# untitled.net
KiCad netlist of a schematic drawn in EAGLE
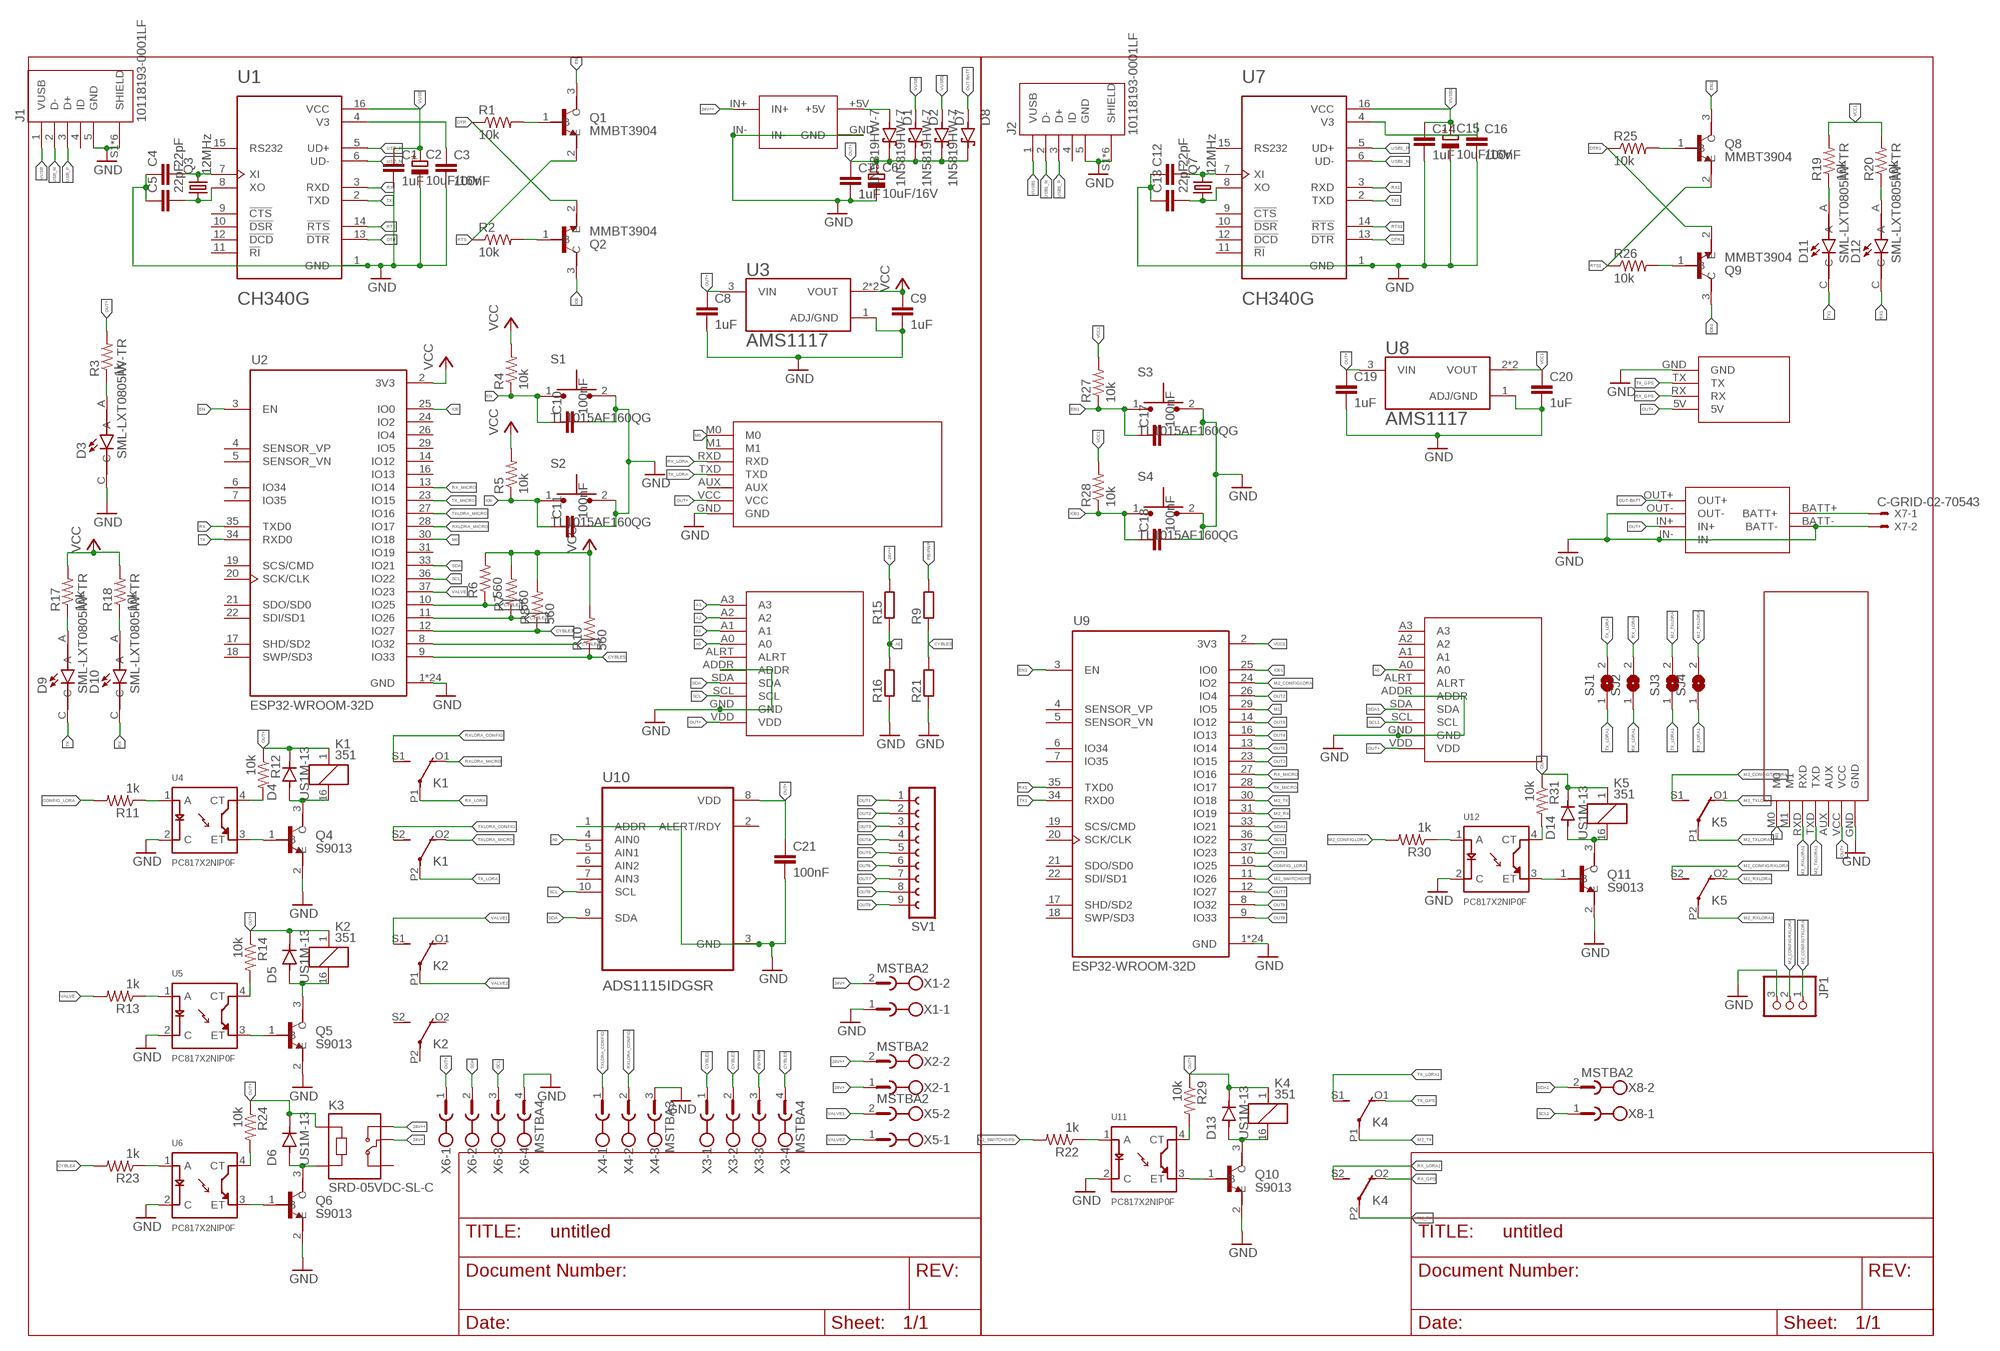
[diagram p0: schematic, sheet 1]

(export (version "E")
  (design (tool "Eeschema 10.0.6"))
  (components
    (comp (ref "ADS1")
      (value "ADS1115")
      (footprint "eagle-import:ADS1115")
      (libsource (lib "eagle-import") (part "ADS1115"))
    )
    (comp (ref "ADS2")
      (value "ADS1115")
      (footprint "eagle-import:ADS1115")
      (libsource (lib "eagle-import") (part "ADS1115"))
    )
    (comp (ref "C1")
      (value "1uF")
      (footprint "eagle-import:C0805K")
      (libsource (lib "eagle-import") (part "C-EUC0805K"))
    )
    (comp (ref "C2")
      (value "10uF/16V")
      (footprint "eagle-import:153CLV-0505")
      (libsource (lib "eagle-import") (part "CPOL-EU153CLV-0505"))
    )
    (comp (ref "C3")
      (value "100nF")
      (footprint "eagle-import:C0805K")
      (libsource (lib "eagle-import") (part "C-EUC0805K"))
    )
    (comp (ref "C4")
      (value "22pF")
      (footprint "eagle-import:C0805K")
      (libsource (lib "eagle-import") (part "C-EUC0805K"))
    )
    (comp (ref "C5")
      (value "22pF")
      (footprint "eagle-import:C0805K")
      (libsource (lib "eagle-import") (part "C-EUC0805K"))
    )
    (comp (ref "C6")
      (value "10uF/16V")
      (footprint "eagle-import:153CLV-0505")
      (libsource (lib "eagle-import") (part "CPOL-EU153CLV-0505"))
    )
    (comp (ref "C7")
      (value "1uF")
      (footprint "eagle-import:C0805K")
      (libsource (lib "eagle-import") (part "C-EUC0805K"))
    )
    (comp (ref "C8")
      (value "1uF")
      (footprint "eagle-import:C0805K")
      (libsource (lib "eagle-import") (part "C-EUC0805K"))
    )
    (comp (ref "C9")
      (value "1uF")
      (footprint "eagle-import:C0805K")
      (libsource (lib "eagle-import") (part "C-EUC0805K"))
    )
    (comp (ref "C10")
      (value "100nF")
      (footprint "eagle-import:C0805K")
      (libsource (lib "eagle-import") (part "C-EUC0805K"))
    )
    (comp (ref "C11")
      (value "100nF")
      (footprint "eagle-import:C0805K")
      (libsource (lib "eagle-import") (part "C-EUC0805K"))
    )
    (comp (ref "C12")
      (value "22pF")
      (footprint "eagle-import:C0805K")
      (libsource (lib "eagle-import") (part "C-EUC0805K"))
    )
    (comp (ref "C13")
      (value "22pF")
      (footprint "eagle-import:C0805K")
      (libsource (lib "eagle-import") (part "C-EUC0805K"))
    )
    (comp (ref "C14")
      (value "1uF")
      (footprint "eagle-import:C0805K")
      (libsource (lib "eagle-import") (part "C-EUC0805K"))
    )
    (comp (ref "C15")
      (value "10uF/16V")
      (footprint "eagle-import:153CLV-0505")
      (libsource (lib "eagle-import") (part "CPOL-EU153CLV-0505"))
    )
    (comp (ref "C16")
      (value "100nF")
      (footprint "eagle-import:C0805K")
      (libsource (lib "eagle-import") (part "C-EUC0805K"))
    )
    (comp (ref "C17")
      (value "100nF")
      (footprint "eagle-import:C0805K")
      (libsource (lib "eagle-import") (part "C-EUC0805K"))
    )
    (comp (ref "C18")
      (value "100nF")
      (footprint "eagle-import:C0805K")
      (libsource (lib "eagle-import") (part "C-EUC0805K"))
    )
    (comp (ref "C19")
      (value "1uF")
      (footprint "eagle-import:C0805K")
      (libsource (lib "eagle-import") (part "C-EUC0805K"))
    )
    (comp (ref "C20")
      (value "1uF")
      (footprint "eagle-import:C0805K")
      (libsource (lib "eagle-import") (part "C-EUC0805K"))
    )
    (comp (ref "C21")
      (value "100nF")
      (footprint "eagle-import:C0805K")
      (libsource (lib "eagle-import") (part "C-EUC0805K"))
    )
    (comp (ref "D1")
      (value "1N5819HW-7")
      (footprint "eagle-import:SOD3715X145N")
      (fields (field (name "MF") "Diodes Inc."))
      (libsource (lib "eagle-import") (part "1N5819HW-7"))
    )
    (comp (ref "D2")
      (value "1N5819HW-7")
      (footprint "eagle-import:SOD3715X145N")
      (fields (field (name "MF") "Diodes Inc."))
      (libsource (lib "eagle-import") (part "1N5819HW-7"))
    )
    (comp (ref "D3")
      (value "SML-LXT0805IW-TR")
      (footprint "eagle-import:LEDC2012X120N")
      (fields (field (name "MF") "Lumex Opto/Components"))
      (libsource (lib "eagle-import") (part "SML-LXT0805IW-TR"))
    )
    (comp (ref "D4")
      (value "US1M-13")
      (footprint "eagle-import:DIOM5226X240N")
      (fields (field (name "MF") "Diodes Incorporated"))
      (libsource (lib "eagle-import") (part "US1M-13"))
    )
    (comp (ref "D5")
      (value "US1M-13")
      (footprint "eagle-import:DIOM5226X240N")
      (fields (field (name "MF") "Diodes Incorporated"))
      (libsource (lib "eagle-import") (part "US1M-13"))
    )
    (comp (ref "D6")
      (value "US1M-13")
      (footprint "eagle-import:DIOM5226X240N")
      (fields (field (name "MF") "Diodes Incorporated"))
      (libsource (lib "eagle-import") (part "US1M-13"))
    )
    (comp (ref "D7")
      (value "1N5819HW-7")
      (footprint "eagle-import:SOD3715X145N")
      (fields (field (name "MF") "Diodes Inc."))
      (libsource (lib "eagle-import") (part "1N5819HW-7"))
    )
    (comp (ref "D8")
      (value "1N5819HW-7")
      (footprint "eagle-import:SOD3715X145N")
      (fields (field (name "MF") "Diodes Inc."))
      (libsource (lib "eagle-import") (part "1N5819HW-7"))
    )
    (comp (ref "D9")
      (value "SML-LXT0805IW-TR")
      (footprint "eagle-import:LEDC2012X120N")
      (fields (field (name "MF") "Lumex Opto/Components"))
      (libsource (lib "eagle-import") (part "SML-LXT0805IW-TR"))
    )
    (comp (ref "D10")
      (value "SML-LXT0805IW-TR")
      (footprint "eagle-import:LEDC2012X120N")
      (fields (field (name "MF") "Lumex Opto/Components"))
      (libsource (lib "eagle-import") (part "SML-LXT0805IW-TR"))
    )
    (comp (ref "D11")
      (value "SML-LXT0805IW-TR")
      (footprint "eagle-import:LEDC2012X120N")
      (fields (field (name "MF") "Lumex Opto/Components"))
      (libsource (lib "eagle-import") (part "SML-LXT0805IW-TR"))
    )
    (comp (ref "D12")
      (value "SML-LXT0805IW-TR")
      (footprint "eagle-import:LEDC2012X120N")
      (fields (field (name "MF") "Lumex Opto/Components"))
      (libsource (lib "eagle-import") (part "SML-LXT0805IW-TR"))
    )
    (comp (ref "D13")
      (value "US1M-13")
      (footprint "eagle-import:DIOM5226X240N")
      (fields (field (name "MF") "Diodes Incorporated"))
      (libsource (lib "eagle-import") (part "US1M-13"))
    )
    (comp (ref "D14")
      (value "US1M-13")
      (footprint "eagle-import:DIOM5226X240N")
      (fields (field (name "MF") "Diodes Incorporated"))
      (libsource (lib "eagle-import") (part "US1M-13"))
    )
    (comp (ref "EBYTEE220-900T22D1")
      (value "EBYTEE220-900T22D")
      (footprint "eagle-import:EBYTEE220-900T22D")
      (libsource (lib "eagle-import") (part "EBYTEE220-900T22D"))
    )
    (comp (ref "EBYTEE220-900T22D2")
      (value "EBYTEE220-900T22D")
      (footprint "eagle-import:EBYTEE220-900T22D")
      (libsource (lib "eagle-import") (part "EBYTEE220-900T22D"))
    )
    (comp (ref "J1")
      (value "10118193-0001LF")
      (footprint "eagle-import:FCI_10118193-0001LF")
      (fields (field (name "MF") "FCI"))
      (libsource (lib "eagle-import") (part "10118193-0001LF"))
    )
    (comp (ref "J2")
      (value "10118193-0001LF")
      (footprint "eagle-import:FCI_10118193-0001LF")
      (fields (field (name "MF") "FCI"))
      (libsource (lib "eagle-import") (part "10118193-0001LF"))
    )
    (comp (ref "JP1")
      (value "PINHD-1X3")
      (footprint "eagle-import:1X03")
      (libsource (lib "eagle-import") (part "PINHD-1X3"))
    )
    (comp (ref "K1")
      (value "351")
      (footprint "eagle-import:351")
      (libsource (lib "eagle-import") (part "351"))
    )
    (comp (ref "K2")
      (value "351")
      (footprint "eagle-import:351")
      (libsource (lib "eagle-import") (part "351"))
    )
    (comp (ref "K3")
      (value "SRD-05VDC-SL-C")
      (footprint "eagle-import:RELAY_SRD-05VDC-SL-C")
      (fields (field (name "MF") "Songle Relay"))
      (libsource (lib "eagle-import") (part "SRD-05VDC-SL-C"))
    )
    (comp (ref "K4")
      (value "351")
      (footprint "eagle-import:351")
      (libsource (lib "eagle-import") (part "351"))
    )
    (comp (ref "K5")
      (value "351")
      (footprint "eagle-import:351")
      (libsource (lib "eagle-import") (part "351"))
    )
    (comp (ref "MODUL-BATT1")
      (value "MODUL-BATT")
      (footprint "eagle-import:MODUL-BATT")
      (libsource (lib "eagle-import") (part "MODUL-BATT"))
    )
    (comp (ref "NEO-6MGPS1")
      (value "NEO-6MGPS")
      (footprint "eagle-import:NEO-6MGPS")
      (libsource (lib "eagle-import") (part "NEO-6MGPS"))
    )
    (comp (ref "Q1")
      (value "MMBT3904")
      (footprint "eagle-import:SOT95P240X120-3N")
      (fields (field (name "MF") "ON Semiconductor"))
      (libsource (lib "eagle-import") (part "MMBT3904"))
    )
    (comp (ref "Q2")
      (value "MMBT3904")
      (footprint "eagle-import:SOT95P240X120-3N")
      (fields (field (name "MF") "ON Semiconductor"))
      (libsource (lib "eagle-import") (part "MMBT3904"))
    )
    (comp (ref "Q3")
      (value "12MHz")
      (footprint "eagle-import:SM49")
      (libsource (lib "eagle-import") (part "CRYSTALSM49"))
    )
    (comp (ref "Q4")
      (value "S9013")
      (footprint "eagle-import:SOT95P240X120-3N")
      (fields (field (name "MF") "JCET"))
      (libsource (lib "eagle-import") (part "S9013"))
    )
    (comp (ref "Q5")
      (value "S9013")
      (footprint "eagle-import:SOT95P240X120-3N")
      (fields (field (name "MF") "JCET"))
      (libsource (lib "eagle-import") (part "S9013"))
    )
    (comp (ref "Q6")
      (value "S9013")
      (footprint "eagle-import:SOT95P240X120-3N")
      (fields (field (name "MF") "JCET"))
      (libsource (lib "eagle-import") (part "S9013"))
    )
    (comp (ref "Q7")
      (value "12MHz")
      (footprint "eagle-import:SM49")
      (libsource (lib "eagle-import") (part "CRYSTALSM49"))
    )
    (comp (ref "Q8")
      (value "MMBT3904")
      (footprint "eagle-import:SOT95P240X120-3N")
      (fields (field (name "MF") "ON Semiconductor"))
      (libsource (lib "eagle-import") (part "MMBT3904"))
    )
    (comp (ref "Q9")
      (value "MMBT3904")
      (footprint "eagle-import:SOT95P240X120-3N")
      (fields (field (name "MF") "ON Semiconductor"))
      (libsource (lib "eagle-import") (part "MMBT3904"))
    )
    (comp (ref "Q10")
      (value "S9013")
      (footprint "eagle-import:SOT95P240X120-3N")
      (fields (field (name "MF") "JCET"))
      (libsource (lib "eagle-import") (part "S9013"))
    )
    (comp (ref "Q11")
      (value "S9013")
      (footprint "eagle-import:SOT95P240X120-3N")
      (fields (field (name "MF") "JCET"))
      (libsource (lib "eagle-import") (part "S9013"))
    )
    (comp (ref "R1")
      (value "10k")
      (footprint "eagle-import:M0805")
      (libsource (lib "eagle-import") (part "R-US_M0805"))
    )
    (comp (ref "R2")
      (value "10k")
      (footprint "eagle-import:M0805")
      (libsource (lib "eagle-import") (part "R-US_M0805"))
    )
    (comp (ref "R3")
      (value "1k")
      (footprint "eagle-import:M0805")
      (libsource (lib "eagle-import") (part "R-US_M0805"))
    )
    (comp (ref "R4")
      (value "10k")
      (footprint "eagle-import:M0805")
      (libsource (lib "eagle-import") (part "R-US_M0805"))
    )
    (comp (ref "R5")
      (value "10k")
      (footprint "eagle-import:M0805")
      (libsource (lib "eagle-import") (part "R-US_M0805"))
    )
    (comp (ref "R6")
      (value "560")
      (footprint "eagle-import:M0805")
      (libsource (lib "eagle-import") (part "R-US_M0805"))
    )
    (comp (ref "R7")
      (value "560")
      (footprint "eagle-import:M0805")
      (libsource (lib "eagle-import") (part "R-US_M0805"))
    )
    (comp (ref "R8")
      (value "560")
      (footprint "eagle-import:M0805")
      (libsource (lib "eagle-import") (part "R-US_M0805"))
    )
    (comp (ref "R9")
      (value "R-EU_0207/12")
      (footprint "eagle-import:0207_12")
      (libsource (lib "eagle-import") (part "R-EU_0207/12"))
    )
    (comp (ref "R10")
      (value "560")
      (footprint "eagle-import:M0805")
      (libsource (lib "eagle-import") (part "R-US_M0805"))
    )
    (comp (ref "R11")
      (value "1k")
      (footprint "eagle-import:M0805")
      (libsource (lib "eagle-import") (part "R-US_M0805"))
    )
    (comp (ref "R12")
      (value "10k")
      (footprint "eagle-import:M0805")
      (libsource (lib "eagle-import") (part "R-US_M0805"))
    )
    (comp (ref "R13")
      (value "1k")
      (footprint "eagle-import:M0805")
      (libsource (lib "eagle-import") (part "R-US_M0805"))
    )
    (comp (ref "R14")
      (value "10k")
      (footprint "eagle-import:M0805")
      (libsource (lib "eagle-import") (part "R-US_M0805"))
    )
    (comp (ref "R15")
      (value "R-EU_0207/12")
      (footprint "eagle-import:0207_12")
      (libsource (lib "eagle-import") (part "R-EU_0207/12"))
    )
    (comp (ref "R16")
      (value "R-EU_0207/12")
      (footprint "eagle-import:0207_12")
      (libsource (lib "eagle-import") (part "R-EU_0207/12"))
    )
    (comp (ref "R17")
      (value "10k")
      (footprint "eagle-import:M0805")
      (libsource (lib "eagle-import") (part "R-US_M0805"))
    )
    (comp (ref "R18")
      (value "10k")
      (footprint "eagle-import:M0805")
      (libsource (lib "eagle-import") (part "R-US_M0805"))
    )
    (comp (ref "R19")
      (value "10k")
      (footprint "eagle-import:M0805")
      (libsource (lib "eagle-import") (part "R-US_M0805"))
    )
    (comp (ref "R20")
      (value "10k")
      (footprint "eagle-import:M0805")
      (libsource (lib "eagle-import") (part "R-US_M0805"))
    )
    (comp (ref "R21")
      (value "R-EU_0207/12")
      (footprint "eagle-import:0207_12")
      (libsource (lib "eagle-import") (part "R-EU_0207/12"))
    )
    (comp (ref "R22")
      (value "1k")
      (footprint "eagle-import:M0805")
      (libsource (lib "eagle-import") (part "R-US_M0805"))
    )
    (comp (ref "R23")
      (value "1k")
      (footprint "eagle-import:M0805")
      (libsource (lib "eagle-import") (part "R-US_M0805"))
    )
    (comp (ref "R24")
      (value "10k")
      (footprint "eagle-import:M0805")
      (libsource (lib "eagle-import") (part "R-US_M0805"))
    )
    (comp (ref "R25")
      (value "10k")
      (footprint "eagle-import:M0805")
      (libsource (lib "eagle-import") (part "R-US_M0805"))
    )
    (comp (ref "R26")
      (value "10k")
      (footprint "eagle-import:M0805")
      (libsource (lib "eagle-import") (part "R-US_M0805"))
    )
    (comp (ref "R27")
      (value "10k")
      (footprint "eagle-import:M0805")
      (libsource (lib "eagle-import") (part "R-US_M0805"))
    )
    (comp (ref "R28")
      (value "10k")
      (footprint "eagle-import:M0805")
      (libsource (lib "eagle-import") (part "R-US_M0805"))
    )
    (comp (ref "R29")
      (value "10k")
      (footprint "eagle-import:M0805")
      (libsource (lib "eagle-import") (part "R-US_M0805"))
    )
    (comp (ref "R30")
      (value "1k")
      (footprint "eagle-import:M0805")
      (libsource (lib "eagle-import") (part "R-US_M0805"))
    )
    (comp (ref "R31")
      (value "10k")
      (footprint "eagle-import:M0805")
      (libsource (lib "eagle-import") (part "R-US_M0805"))
    )
    (comp (ref "S1")
      (value "TL1015AF160QG")
      (footprint "eagle-import:SW_TL1015AF160QG")
      (fields (field (name "MF") "E-Switch"))
      (libsource (lib "eagle-import") (part "TL1015AF160QG"))
    )
    (comp (ref "S2")
      (value "TL1015AF160QG")
      (footprint "eagle-import:SW_TL1015AF160QG")
      (fields (field (name "MF") "E-Switch"))
      (libsource (lib "eagle-import") (part "TL1015AF160QG"))
    )
    (comp (ref "S3")
      (value "TL1015AF160QG")
      (footprint "eagle-import:SW_TL1015AF160QG")
      (fields (field (name "MF") "E-Switch"))
      (libsource (lib "eagle-import") (part "TL1015AF160QG"))
    )
    (comp (ref "S4")
      (value "TL1015AF160QG")
      (footprint "eagle-import:SW_TL1015AF160QG")
      (fields (field (name "MF") "E-Switch"))
      (libsource (lib "eagle-import") (part "TL1015AF160QG"))
    )
    (comp (ref "SJ1") (value "SJ") (footprint "eagle-import:SJ") (libsource (lib "eagle-import") (part "SJ")))
    (comp (ref "SJ2") (value "SJ") (footprint "eagle-import:SJ") (libsource (lib "eagle-import") (part "SJ")))
    (comp (ref "SJ3") (value "SJ") (footprint "eagle-import:SJ") (libsource (lib "eagle-import") (part "SJ")))
    (comp (ref "SJ4") (value "SJ") (footprint "eagle-import:SJ") (libsource (lib "eagle-import") (part "SJ")))
    (comp (ref "SUPER-STEPDOWN1")
      (value "SUPER-STEPDOWN")
      (footprint "eagle-import:SUPER-STEPDOWN")
      (libsource (lib "eagle-import") (part "SUPER-STEPDOWN"))
    )
    (comp (ref "SV1")
      (value "FE09-1")
      (footprint "eagle-import:FE09")
      (libsource (lib "eagle-import") (part "FE09-1"))
    )
    (comp (ref "U1")
      (value "CH340G")
      (footprint "eagle-import:SOIC127P600X180-16N")
      (fields (field (name "MF") "WCH") (field (name "MP") "Ch340G"))
      (libsource (lib "eagle-import") (part "CH340G"))
    )
    (comp (ref "U2")
      (value "ESP32-WROOM-32D")
      (footprint "eagle-import:MODULE_ESP32-WROOM-32D")
      (fields (field (name "MF") "Espressif Systems"))
      (libsource (lib "eagle-import") (part "ESP32-WROOM-32D"))
    )
    (comp (ref "U3")
      (value "AMS1117")
      (footprint "eagle-import:SOT229P700X180-4N")
      (fields (field (name "MF") "Advanced Monolithic Systems"))
      (libsource (lib "eagle-import") (part "AMS1117"))
    )
    (comp (ref "U4")
      (value "PC817X2NIP0F")
      (footprint "eagle-import:SOT254P975X400-4N")
      (fields (field (name "MF") "Sharp Microelectronics"))
      (libsource (lib "eagle-import") (part "PC817X2NIP0F"))
    )
    (comp (ref "U5")
      (value "PC817X2NIP0F")
      (footprint "eagle-import:SOT254P975X400-4N")
      (fields (field (name "MF") "Sharp Microelectronics"))
      (libsource (lib "eagle-import") (part "PC817X2NIP0F"))
    )
    (comp (ref "U6")
      (value "PC817X2NIP0F")
      (footprint "eagle-import:SOT254P975X400-4N")
      (fields (field (name "MF") "Sharp Microelectronics"))
      (libsource (lib "eagle-import") (part "PC817X2NIP0F"))
    )
    (comp (ref "U7")
      (value "CH340G")
      (footprint "eagle-import:SOIC127P600X180-16N")
      (fields (field (name "MF") "WCH") (field (name "MP") "Ch340G"))
      (libsource (lib "eagle-import") (part "CH340G"))
    )
    (comp (ref "U8")
      (value "AMS1117")
      (footprint "eagle-import:SOT229P700X180-4N")
      (fields (field (name "MF") "Advanced Monolithic Systems"))
      (libsource (lib "eagle-import") (part "AMS1117"))
    )
    (comp (ref "U9")
      (value "ESP32-WROOM-32D")
      (footprint "eagle-import:MODULE_ESP32-WROOM-32D")
      (fields (field (name "MF") "Espressif Systems"))
      (libsource (lib "eagle-import") (part "ESP32-WROOM-32D"))
    )
    (comp (ref "U10")
      (value "ADS1115IDGSR")
      (footprint "eagle-import:SOP50P490X110-10N")
      (fields (field (name "MF") "Texas Instruments"))
      (libsource (lib "eagle-import") (part "ADS1115IDGSR"))
    )
    (comp (ref "U11")
      (value "PC817X2NIP0F")
      (footprint "eagle-import:SOT254P975X400-4N")
      (fields (field (name "MF") "Sharp Microelectronics"))
      (libsource (lib "eagle-import") (part "PC817X2NIP0F"))
    )
    (comp (ref "U12")
      (value "PC817X2NIP0F")
      (footprint "eagle-import:SOT254P975X400-4N")
      (fields (field (name "MF") "Sharp Microelectronics"))
      (libsource (lib "eagle-import") (part "PC817X2NIP0F"))
    )
    (comp (ref "X1")
      (value "MSTBA2")
      (footprint "eagle-import:MSTBA2")
      (fields (field (name "MF") "FARNELL") (field (name "MPN") "1757242"))
      (libsource (lib "eagle-import") (part "MSTBA2"))
    )
    (comp (ref "X2")
      (value "MSTBA2")
      (footprint "eagle-import:MSTBA2")
      (fields (field (name "MF") "FARNELL") (field (name "MPN") "1757242"))
      (libsource (lib "eagle-import") (part "MSTBA2"))
    )
    (comp (ref "X3")
      (value "MSTBA4")
      (footprint "eagle-import:MSTBA4")
      (fields (field (name "MF") "FARNELL") (field (name "MPN") "1757268"))
      (libsource (lib "eagle-import") (part "MSTBA4"))
    )
    (comp (ref "X4")
      (value "MSTBA3")
      (footprint "eagle-import:MSTBA3")
      (fields (field (name "MF") "FARNELL") (field (name "MPN") "1757255"))
      (libsource (lib "eagle-import") (part "MSTBA3"))
    )
    (comp (ref "X5")
      (value "MSTBA2")
      (footprint "eagle-import:MSTBA2")
      (fields (field (name "MF") "FARNELL") (field (name "MPN") "1757242"))
      (libsource (lib "eagle-import") (part "MSTBA2"))
    )
    (comp (ref "X6")
      (value "MSTBA4")
      (footprint "eagle-import:MSTBA4")
      (fields (field (name "MF") "FARNELL") (field (name "MPN") "1757268"))
      (libsource (lib "eagle-import") (part "MSTBA4"))
    )
    (comp (ref "X7")
      (value "C-GRID-02-70543")
      (footprint "eagle-import:70543-02")
      (fields (field (name "MF") "MOLEX"))
      (libsource (lib "eagle-import") (part "C-GRID-02-70543"))
    )
    (comp (ref "X8")
      (value "MSTBA2")
      (footprint "eagle-import:MSTBA2")
      (fields (field (name "MF") "FARNELL") (field (name "MPN") "1757242"))
      (libsource (lib "eagle-import") (part "MSTBA2"))
    )
  )
  (nets
    (net (code "1") (name "24V+") (class "Default")
      (node (ref "K3") (pin "COM") (pinfunction "COM_COM") (pintype "passive"))
      (node (ref "X1") (pin "2") (pinfunction "1_2") (pintype "passive"))
      (node (ref "X2") (pin "1") (pinfunction "1_1") (pintype "passive"))
    )
    (net (code "2") (name "24V++") (class "Default")
      (node (ref "K3") (pin "NO") (pinfunction "NO_NO") (pintype "passive"))
      (node (ref "R15") (pin "2") (pinfunction "2_2") (pintype "passive"))
      (node (ref "SUPER-STEPDOWN1") (pin "IN+") (pinfunction "IN+_IN+") (pintype "bidirectional"))
      (node (ref "X2") (pin "2") (pinfunction "1_2") (pintype "passive"))
    )
    (net (code "3") (name "A0") (class "Default")
      (node (ref "ADS1") (pin "A0") (pinfunction "A0_A0") (pintype "bidirectional"))
      (node (ref "ADS2") (pin "A0") (pinfunction "A0_A0") (pintype "bidirectional"))
      (node (ref "R15") (pin "1") (pinfunction "1_1") (pintype "passive"))
      (node (ref "R16") (pin "2") (pinfunction "2_2") (pintype "passive"))
      (node (ref "U10") (pin "4") (pinfunction "AIN0_4") (pintype "input"))
    )
    (net (code "4") (name "A1") (class "Default")
      (node (ref "ADS1") (pin "A1") (pinfunction "A1_A1") (pintype "bidirectional"))
    )
    (net (code "5") (name "A2") (class "Default")
      (node (ref "ADS1") (pin "A2") (pinfunction "A2_A2") (pintype "bidirectional"))
    )
    (net (code "6") (name "A3") (class "Default")
      (node (ref "ADS1") (pin "A3") (pinfunction "A3_A3") (pintype "bidirectional"))
    )
    (net (code "7") (name "CONFIG_LORA") (class "Default")
      (node (ref "R11") (pin "2") (pinfunction "2_2") (pintype "passive"))
      (node (ref "U9") (pin "10") (pinfunction "IO25_10") (pintype "bidirectional"))
    )
    (net (code "8") (name "CYBLE1") (class "Default")
      (node (ref "R6") (pin "1") (pinfunction "1_1") (pintype "passive"))
      (node (ref "U2") (pin "10") (pinfunction "IO25_10") (pintype "bidirectional"))
      (node (ref "X3") (pin "1") (pinfunction "1_1") (pintype "passive"))
    )
    (net (code "9") (name "CYBLE2") (class "Default")
      (node (ref "R7") (pin "1") (pinfunction "1_1") (pintype "passive"))
      (node (ref "U2") (pin "11") (pinfunction "IO26_11") (pintype "bidirectional"))
      (node (ref "X3") (pin "2") (pinfunction "1_2") (pintype "passive"))
    )
    (net (code "10") (name "CYBLE3") (class "Default")
      (node (ref "R21") (pin "2") (pinfunction "2_2") (pintype "passive"))
      (node (ref "R8") (pin "1") (pinfunction "1_1") (pintype "passive"))
      (node (ref "R9") (pin "1") (pinfunction "1_1") (pintype "passive"))
      (node (ref "U2") (pin "12") (pinfunction "IO27_12") (pintype "bidirectional"))
    )
    (net (code "11") (name "CYBLE4") (class "Default")
      (node (ref "R23") (pin "2") (pinfunction "2_2") (pintype "passive"))
      (node (ref "U2") (pin "8") (pinfunction "IO32_8") (pintype "bidirectional"))
    )
    (net (code "12") (name "CYBLE5") (class "Default")
      (node (ref "R10") (pin "1") (pinfunction "1_1") (pintype "passive"))
      (node (ref "U2") (pin "9") (pinfunction "IO33_9") (pintype "bidirectional"))
      (node (ref "X3") (pin "4") (pinfunction "1_4") (pintype "passive"))
    )
    (net (code "13") (name "DTR") (class "Default")
      (node (ref "Q2") (pin "2") (pinfunction "E_2") (pintype "passive"))
      (node (ref "R1") (pin "1") (pinfunction "1_1") (pintype "passive"))
      (node (ref "U1") (pin "13") (pinfunction "~{DTR}_13") (pintype "output"))
    )
    (net (code "14") (name "DTR1") (class "Default")
      (node (ref "Q9") (pin "2") (pinfunction "E_2") (pintype "passive"))
      (node (ref "R25") (pin "1") (pinfunction "1_1") (pintype "passive"))
      (node (ref "U7") (pin "13") (pinfunction "~{DTR}_13") (pintype "output"))
    )
    (net (code "15") (name "EN") (class "Default")
      (node (ref "C10") (pin "1") (pinfunction "1_1") (pintype "passive"))
      (node (ref "Q1") (pin "3") (pinfunction "C_3") (pintype "passive"))
      (node (ref "R4") (pin "1") (pinfunction "1_1") (pintype "passive"))
      (node (ref "S1") (pin "1") (pinfunction "1_1") (pintype "passive"))
      (node (ref "U2") (pin "3") (pinfunction "EN_3") (pintype "input"))
    )
    (net (code "16") (name "EN1") (class "Default")
      (node (ref "C17") (pin "1") (pinfunction "1_1") (pintype "passive"))
      (node (ref "Q8") (pin "3") (pinfunction "C_3") (pintype "passive"))
      (node (ref "R27") (pin "1") (pinfunction "1_1") (pintype "passive"))
      (node (ref "S3") (pin "1") (pinfunction "1_1") (pintype "passive"))
      (node (ref "U9") (pin "3") (pinfunction "EN_3") (pintype "input"))
    )
    (net (code "17") (name "GND") (class "Default")
      (node (ref "ADS1") (pin "ADDR") (pinfunction "ADDR_ADDR") (pintype "bidirectional"))
      (node (ref "ADS1") (pin "GND") (pinfunction "GND_GND") (pintype "bidirectional"))
      (node (ref "ADS2") (pin "ADDR") (pinfunction "ADDR_ADDR") (pintype "bidirectional"))
      (node (ref "ADS2") (pin "GND") (pinfunction "GND_GND") (pintype "bidirectional"))
      (node (ref "C1") (pin "2") (pinfunction "2_2") (pintype "passive"))
      (node (ref "C10") (pin "2") (pinfunction "2_2") (pintype "passive"))
      (node (ref "C11") (pin "2") (pinfunction "2_2") (pintype "passive"))
      (node (ref "C12") (pin "1") (pinfunction "1_1") (pintype "passive"))
      (node (ref "C13") (pin "1") (pinfunction "1_1") (pintype "passive"))
      (node (ref "C14") (pin "2") (pinfunction "2_2") (pintype "passive"))
      (node (ref "C15") (pin "-") (pinfunction "-_-") (pintype "passive"))
      (node (ref "C16") (pin "2") (pinfunction "2_2") (pintype "passive"))
      (node (ref "C17") (pin "2") (pinfunction "2_2") (pintype "passive"))
      (node (ref "C18") (pin "2") (pinfunction "2_2") (pintype "passive"))
      (node (ref "C19") (pin "2") (pinfunction "2_2") (pintype "passive"))
      (node (ref "C2") (pin "-") (pinfunction "-_-") (pintype "passive"))
      (node (ref "C20") (pin "2") (pinfunction "2_2") (pintype "passive"))
      (node (ref "C21") (pin "2") (pinfunction "2_2") (pintype "passive"))
      (node (ref "C3") (pin "2") (pinfunction "2_2") (pintype "passive"))
      (node (ref "C4") (pin "1") (pinfunction "1_1") (pintype "passive"))
      (node (ref "C5") (pin "1") (pinfunction "1_1") (pintype "passive"))
      (node (ref "C6") (pin "-") (pinfunction "-_-") (pintype "passive"))
      (node (ref "C7") (pin "2") (pinfunction "2_2") (pintype "passive"))
      (node (ref "C8") (pin "2") (pinfunction "2_2") (pintype "passive"))
      (node (ref "C9") (pin "2") (pinfunction "2_2") (pintype "passive"))
      (node (ref "D3") (pin "C") (pinfunction "C_C") (pintype "passive"))
      (node (ref "EBYTEE220-900T22D1") (pin "GND") (pinfunction "GND_GND") (pintype "bidirectional"))
      (node (ref "EBYTEE220-900T22D2") (pin "GND") (pinfunction "GND_GND") (pintype "bidirectional"))
      (node (ref "J1") (pin "5") (pinfunction "GND_5") (pintype "passive"))
      (node (ref "J1") (pin "S1") (pinfunction "SHIELD_S1") (pintype "passive"))
      (node (ref "J1") (pin "S2") (pinfunction "SHIELD_S2") (pintype "passive"))
      (node (ref "J1") (pin "S3") (pinfunction "SHIELD_S3") (pintype "passive"))
      (node (ref "J1") (pin "S4") (pinfunction "SHIELD_S4") (pintype "passive"))
      (node (ref "J1") (pin "S5") (pinfunction "SHIELD_S5") (pintype "passive"))
      (node (ref "J1") (pin "S6") (pinfunction "SHIELD_S6") (pintype "passive"))
      (node (ref "J2") (pin "5") (pinfunction "GND_5") (pintype "passive"))
      (node (ref "J2") (pin "S1") (pinfunction "SHIELD_S1") (pintype "passive"))
      (node (ref "J2") (pin "S2") (pinfunction "SHIELD_S2") (pintype "passive"))
      (node (ref "J2") (pin "S3") (pinfunction "SHIELD_S3") (pintype "passive"))
      (node (ref "J2") (pin "S4") (pinfunction "SHIELD_S4") (pintype "passive"))
      (node (ref "J2") (pin "S5") (pinfunction "SHIELD_S5") (pintype "passive"))
      (node (ref "J2") (pin "S6") (pinfunction "SHIELD_S6") (pintype "passive"))
      (node (ref "JP1") (pin "3") (pinfunction "3_3") (pintype "passive"))
      (node (ref "MODUL-BATT1") (pin "BATT-") (pinfunction "BATT-_BATT-") (pintype "bidirectional"))
      (node (ref "MODUL-BATT1") (pin "IN-") (pinfunction "IN-_IN-") (pintype "bidirectional"))
      (node (ref "MODUL-BATT1") (pin "OUT-") (pinfunction "OUT-_OUT-") (pintype "bidirectional"))
      (node (ref "NEO-6MGPS1") (pin "GND") (pinfunction "GND_GND") (pintype "bidirectional"))
      (node (ref "Q10") (pin "2") (pinfunction "E_2") (pintype "passive"))
      (node (ref "Q11") (pin "2") (pinfunction "E_2") (pintype "passive"))
      (node (ref "Q4") (pin "2") (pinfunction "E_2") (pintype "passive"))
      (node (ref "Q5") (pin "2") (pinfunction "E_2") (pintype "passive"))
      (node (ref "Q6") (pin "2") (pinfunction "E_2") (pintype "passive"))
      (node (ref "R16") (pin "1") (pinfunction "1_1") (pintype "passive"))
      (node (ref "R21") (pin "1") (pinfunction "1_1") (pintype "passive"))
      (node (ref "S1") (pin "2") (pinfunction "2_2") (pintype "passive"))
      (node (ref "S2") (pin "2") (pinfunction "2_2") (pintype "passive"))
      (node (ref "S3") (pin "2") (pinfunction "2_2") (pintype "passive"))
      (node (ref "S4") (pin "2") (pinfunction "2_2") (pintype "passive"))
      (node (ref "SUPER-STEPDOWN1") (pin "GND") (pinfunction "GND_GND") (pintype "bidirectional"))
      (node (ref "SUPER-STEPDOWN1") (pin "IN-") (pinfunction "IN-_IN-") (pintype "bidirectional"))
      (node (ref "U1") (pin "1") (pinfunction "GND_1") (pintype "power_in"))
      (node (ref "U10") (pin "1") (pinfunction "ADDR_1") (pintype "input"))
      (node (ref "U10") (pin "3") (pinfunction "GND_3") (pintype "power_in"))
      (node (ref "U11") (pin "2") (pinfunction "C_2") (pintype "passive"))
      (node (ref "U12") (pin "2") (pinfunction "C_2") (pintype "passive"))
      (node (ref "U2") (pin "1") (pinfunction "GND_1") (pintype "power_in"))
      (node (ref "U2") (pin "15") (pinfunction "GND_15") (pintype "power_in"))
      (node (ref "U2") (pin "38") (pinfunction "GND_38") (pintype "power_in"))
      (node (ref "U2") (pin "39_1") (pinfunction "GND_39_1") (pintype "power_in"))
      (node (ref "U2") (pin "39_10") (pinfunction "GND_39_10") (pintype "power_in"))
      (node (ref "U2") (pin "39_11") (pinfunction "GND_39_11") (pintype "power_in"))
      (node (ref "U2") (pin "39_12") (pinfunction "GND_39_12") (pintype "power_in"))
      (node (ref "U2") (pin "39_13") (pinfunction "GND_39_13") (pintype "power_in"))
      (node (ref "U2") (pin "39_14") (pinfunction "GND_39_14") (pintype "power_in"))
      (node (ref "U2") (pin "39_15") (pinfunction "GND_39_15") (pintype "power_in"))
      (node (ref "U2") (pin "39_16") (pinfunction "GND_39_16") (pintype "power_in"))
      (node (ref "U2") (pin "39_17") (pinfunction "GND_39_17") (pintype "power_in"))
      (node (ref "U2") (pin "39_18") (pinfunction "GND_39_18") (pintype "power_in"))
      (node (ref "U2") (pin "39_19") (pinfunction "GND_39_19") (pintype "power_in"))
      (node (ref "U2") (pin "39_2") (pinfunction "GND_39_2") (pintype "power_in"))
      (node (ref "U2") (pin "39_20") (pinfunction "GND_39_20") (pintype "power_in"))
      (node (ref "U2") (pin "39_21") (pinfunction "GND_39_21") (pintype "power_in"))
      (node (ref "U2") (pin "39_3") (pinfunction "GND_39_3") (pintype "power_in"))
      (node (ref "U2") (pin "39_4") (pinfunction "GND_39_4") (pintype "power_in"))
      (node (ref "U2") (pin "39_5") (pinfunction "GND_39_5") (pintype "power_in"))
      (node (ref "U2") (pin "39_6") (pinfunction "GND_39_6") (pintype "power_in"))
      (node (ref "U2") (pin "39_7") (pinfunction "GND_39_7") (pintype "power_in"))
      (node (ref "U2") (pin "39_8") (pinfunction "GND_39_8") (pintype "power_in"))
      (node (ref "U2") (pin "39_9") (pinfunction "GND_39_9") (pintype "power_in"))
      (node (ref "U3") (pin "1") (pinfunction "ADJ/GND_1") (pintype "power_in"))
      (node (ref "U4") (pin "2") (pinfunction "C_2") (pintype "passive"))
      (node (ref "U5") (pin "2") (pinfunction "C_2") (pintype "passive"))
      (node (ref "U6") (pin "2") (pinfunction "C_2") (pintype "passive"))
      (node (ref "U7") (pin "1") (pinfunction "GND_1") (pintype "power_in"))
      (node (ref "U8") (pin "1") (pinfunction "ADJ/GND_1") (pintype "power_in"))
      (node (ref "U9") (pin "1") (pinfunction "GND_1") (pintype "power_in"))
      (node (ref "U9") (pin "15") (pinfunction "GND_15") (pintype "power_in"))
      (node (ref "U9") (pin "38") (pinfunction "GND_38") (pintype "power_in"))
      (node (ref "U9") (pin "39_1") (pinfunction "GND_39_1") (pintype "power_in"))
      (node (ref "U9") (pin "39_10") (pinfunction "GND_39_10") (pintype "power_in"))
      (node (ref "U9") (pin "39_11") (pinfunction "GND_39_11") (pintype "power_in"))
      (node (ref "U9") (pin "39_12") (pinfunction "GND_39_12") (pintype "power_in"))
      (node (ref "U9") (pin "39_13") (pinfunction "GND_39_13") (pintype "power_in"))
      (node (ref "U9") (pin "39_14") (pinfunction "GND_39_14") (pintype "power_in"))
      (node (ref "U9") (pin "39_15") (pinfunction "GND_39_15") (pintype "power_in"))
      (node (ref "U9") (pin "39_16") (pinfunction "GND_39_16") (pintype "power_in"))
      (node (ref "U9") (pin "39_17") (pinfunction "GND_39_17") (pintype "power_in"))
      (node (ref "U9") (pin "39_18") (pinfunction "GND_39_18") (pintype "power_in"))
      (node (ref "U9") (pin "39_19") (pinfunction "GND_39_19") (pintype "power_in"))
      (node (ref "U9") (pin "39_2") (pinfunction "GND_39_2") (pintype "power_in"))
      (node (ref "U9") (pin "39_20") (pinfunction "GND_39_20") (pintype "power_in"))
      (node (ref "U9") (pin "39_21") (pinfunction "GND_39_21") (pintype "power_in"))
      (node (ref "U9") (pin "39_3") (pinfunction "GND_39_3") (pintype "power_in"))
      (node (ref "U9") (pin "39_4") (pinfunction "GND_39_4") (pintype "power_in"))
      (node (ref "U9") (pin "39_5") (pinfunction "GND_39_5") (pintype "power_in"))
      (node (ref "U9") (pin "39_6") (pinfunction "GND_39_6") (pintype "power_in"))
      (node (ref "U9") (pin "39_7") (pinfunction "GND_39_7") (pintype "power_in"))
      (node (ref "U9") (pin "39_8") (pinfunction "GND_39_8") (pintype "power_in"))
      (node (ref "U9") (pin "39_9") (pinfunction "GND_39_9") (pintype "power_in"))
      (node (ref "X1") (pin "1") (pinfunction "1_1") (pintype "passive"))
      (node (ref "X4") (pin "3") (pinfunction "1_3") (pintype "passive"))
      (node (ref "X6") (pin "4") (pinfunction "1_4") (pintype "passive"))
      (node (ref "X7") (pin "2") (pinfunction "S_2") (pintype "passive"))
    )
    (net (code "18") (name "IO0") (class "Default")
      (node (ref "C11") (pin "1") (pinfunction "1_1") (pintype "passive"))
      (node (ref "Q2") (pin "3") (pinfunction "C_3") (pintype "passive"))
      (node (ref "R5") (pin "1") (pinfunction "1_1") (pintype "passive"))
      (node (ref "S2") (pin "1") (pinfunction "1_1") (pintype "passive"))
      (node (ref "U2") (pin "25") (pinfunction "IO0_25") (pintype "bidirectional"))
    )
    (net (code "19") (name "IO01") (class "Default")
      (node (ref "C18") (pin "1") (pinfunction "1_1") (pintype "passive"))
      (node (ref "Q9") (pin "3") (pinfunction "C_3") (pintype "passive"))
      (node (ref "R28") (pin "1") (pinfunction "1_1") (pintype "passive"))
      (node (ref "S4") (pin "1") (pinfunction "1_1") (pintype "passive"))
      (node (ref "U9") (pin "25") (pinfunction "IO0_25") (pintype "bidirectional"))
    )
    (net (code "20") (name "M0") (class "Default")
      (node (ref "EBYTEE220-900T22D1") (pin "M0") (pinfunction "M0_M0") (pintype "bidirectional"))
      (node (ref "EBYTEE220-900T22D1") (pin "M1") (pinfunction "M1_M1") (pintype "bidirectional"))
      (node (ref "U2") (pin "30") (pinfunction "IO18_30") (pintype "bidirectional"))
    )
    (net (code "21") (name "M1") (class "Default")
      (node (ref "EBYTEE220-900T22D2") (pin "M0") (pinfunction "M0_M0") (pintype "bidirectional"))
      (node (ref "EBYTEE220-900T22D2") (pin "M1") (pinfunction "M1_M1") (pintype "bidirectional"))
      (node (ref "U9") (pin "29") (pinfunction "IO5_29") (pintype "bidirectional"))
    )
    (net (code "22") (name "M2_CONFIGLORA") (class "Default")
      (node (ref "R30") (pin "2") (pinfunction "2_2") (pintype "passive"))
      (node (ref "U9") (pin "24") (pinfunction "IO2_24") (pintype "bidirectional"))
    )
    (net (code "23") (name "M2_CONFIGRXLORA") (class "Default")
      (node (ref "JP1") (pin "2") (pinfunction "2_2") (pintype "passive"))
      (node (ref "K5") (pin "S2") (pinfunction "S_S2") (pintype "passive"))
    )
    (net (code "24") (name "M2_CONFIGTXLORA") (class "Default")
      (node (ref "JP1") (pin "1") (pinfunction "1_1") (pintype "passive"))
      (node (ref "K5") (pin "S1") (pinfunction "S_S1") (pintype "passive"))
    )
    (net (code "25") (name "M2_RX") (class "Default")
      (node (ref "K4") (pin "P2") (pinfunction "P_P2") (pintype "passive"))
      (node (ref "U9") (pin "31") (pinfunction "IO19_31") (pintype "bidirectional"))
    )
    (net (code "26") (name "M2_RXLORA") (class "Default")
      (node (ref "K5") (pin "O2") (pinfunction "O_O2") (pintype "passive"))
      (node (ref "SJ4") (pin "2") (pinfunction "2_2") (pintype "passive"))
    )
    (net (code "27") (name "M2_RXLORA1") (class "Default")
      (node (ref "EBYTEE220-900T22D2") (pin "RXD") (pinfunction "RXD_RXD") (pintype "bidirectional"))
      (node (ref "K5") (pin "P2") (pinfunction "P_P2") (pintype "passive"))
    )
    (net (code "28") (name "M2_SWITCHGPS") (class "Default")
      (node (ref "R22") (pin "2") (pinfunction "2_2") (pintype "passive"))
      (node (ref "U9") (pin "11") (pinfunction "IO26_11") (pintype "bidirectional"))
    )
    (net (code "29") (name "M2_TX") (class "Default")
      (node (ref "K4") (pin "P1") (pinfunction "P_P1") (pintype "passive"))
      (node (ref "U9") (pin "30") (pinfunction "IO18_30") (pintype "bidirectional"))
    )
    (net (code "30") (name "M2_TXLORA") (class "Default")
      (node (ref "K5") (pin "O1") (pinfunction "O_O1") (pintype "passive"))
      (node (ref "SJ3") (pin "2") (pinfunction "2_2") (pintype "passive"))
    )
    (net (code "31") (name "M2_TXLORA1") (class "Default")
      (node (ref "EBYTEE220-900T22D2") (pin "TXD") (pinfunction "TXD_TXD") (pintype "bidirectional"))
      (node (ref "K5") (pin "P1") (pinfunction "P_P1") (pintype "passive"))
    )
    (net (code "32") (name "Net-(D1-PadA)") (class "Default")
      (node (ref "D1") (pin "A") (pinfunction "A_A") (pintype "passive"))
      (node (ref "SUPER-STEPDOWN1") (pin "+5V") (pinfunction "+5V_+5V") (pintype "bidirectional"))
    )
    (net (code "33") (name "Net-(D3-PadA)") (class "Default")
      (node (ref "D3") (pin "A") (pinfunction "A_A") (pintype "passive"))
      (node (ref "R3") (pin "1") (pinfunction "1_1") (pintype "passive"))
    )
    (net (code "34") (name "Net-(D9-PadA)") (class "Default")
      (node (ref "D9") (pin "A") (pinfunction "A_A") (pintype "passive"))
      (node (ref "R17") (pin "1") (pinfunction "1_1") (pintype "passive"))
    )
    (net (code "35") (name "Net-(D10-PadA)") (class "Default")
      (node (ref "D10") (pin "A") (pinfunction "A_A") (pintype "passive"))
      (node (ref "R18") (pin "1") (pinfunction "1_1") (pintype "passive"))
    )
    (net (code "36") (name "Net-(D11-PadA)") (class "Default")
      (node (ref "D11") (pin "A") (pinfunction "A_A") (pintype "passive"))
      (node (ref "R19") (pin "1") (pinfunction "1_1") (pintype "passive"))
    )
    (net (code "37") (name "Net-(D12-PadA)") (class "Default")
      (node (ref "D12") (pin "A") (pinfunction "A_A") (pintype "passive"))
      (node (ref "R20") (pin "1") (pinfunction "1_1") (pintype "passive"))
    )
    (net (code "38") (name "Net-(K1A-2)") (class "Default")
      (node (ref "D4") (pin "A") (pinfunction "A_A") (pintype "passive"))
      (node (ref "K1") (pin "16") (pinfunction "2_16") (pintype "passive"))
      (node (ref "Q4") (pin "3") (pinfunction "C_3") (pintype "passive"))
    )
    (net (code "39") (name "Net-(K2A-2)") (class "Default")
      (node (ref "D5") (pin "A") (pinfunction "A_A") (pintype "passive"))
      (node (ref "K2") (pin "16") (pinfunction "2_16") (pintype "passive"))
      (node (ref "Q5") (pin "3") (pinfunction "C_3") (pintype "passive"))
    )
    (net (code "40") (name "Net-(K4A-2)") (class "Default")
      (node (ref "D13") (pin "A") (pinfunction "A_A") (pintype "passive"))
      (node (ref "K4") (pin "16") (pinfunction "2_16") (pintype "passive"))
      (node (ref "Q10") (pin "3") (pinfunction "C_3") (pintype "passive"))
    )
    (net (code "41") (name "Net-(K5A-2)") (class "Default")
      (node (ref "D14") (pin "A") (pinfunction "A_A") (pintype "passive"))
      (node (ref "K5") (pin "16") (pinfunction "2_16") (pintype "passive"))
      (node (ref "Q11") (pin "3") (pinfunction "C_3") (pintype "passive"))
    )
    (net (code "42") (name "Net-(Q1-B)") (class "Default")
      (node (ref "Q1") (pin "1") (pinfunction "B_1") (pintype "passive"))
      (node (ref "R1") (pin "2") (pinfunction "2_2") (pintype "passive"))
    )
    (net (code "43") (name "Net-(Q2-B)") (class "Default")
      (node (ref "Q2") (pin "1") (pinfunction "B_1") (pintype "passive"))
      (node (ref "R2") (pin "2") (pinfunction "2_2") (pintype "passive"))
    )
    (net (code "44") (name "Net-(Q4-B)") (class "Default")
      (node (ref "Q4") (pin "1") (pinfunction "B_1") (pintype "passive"))
      (node (ref "U4") (pin "3") (pinfunction "ET_3") (pintype "passive"))
    )
    (net (code "45") (name "Net-(Q5-B)") (class "Default")
      (node (ref "Q5") (pin "1") (pinfunction "B_1") (pintype "passive"))
      (node (ref "U5") (pin "3") (pinfunction "ET_3") (pintype "passive"))
    )
    (net (code "46") (name "Net-(Q6-B)") (class "Default")
      (node (ref "Q6") (pin "1") (pinfunction "B_1") (pintype "passive"))
      (node (ref "U6") (pin "3") (pinfunction "ET_3") (pintype "passive"))
    )
    (net (code "47") (name "Net-(Q6-C)") (class "Default")
      (node (ref "D6") (pin "A") (pinfunction "A_A") (pintype "passive"))
      (node (ref "K3") (pin "A2") (pinfunction "A2_A2") (pintype "passive"))
      (node (ref "Q6") (pin "3") (pinfunction "C_3") (pintype "passive"))
    )
    (net (code "48") (name "Net-(Q8-B)") (class "Default")
      (node (ref "Q8") (pin "1") (pinfunction "B_1") (pintype "passive"))
      (node (ref "R25") (pin "2") (pinfunction "2_2") (pintype "passive"))
    )
    (net (code "49") (name "Net-(Q9-B)") (class "Default")
      (node (ref "Q9") (pin "1") (pinfunction "B_1") (pintype "passive"))
      (node (ref "R26") (pin "2") (pinfunction "2_2") (pintype "passive"))
    )
    (net (code "50") (name "Net-(Q10-B)") (class "Default")
      (node (ref "Q10") (pin "1") (pinfunction "B_1") (pintype "passive"))
      (node (ref "U11") (pin "3") (pinfunction "ET_3") (pintype "passive"))
    )
    (net (code "51") (name "Net-(Q11-B)") (class "Default")
      (node (ref "Q11") (pin "1") (pinfunction "B_1") (pintype "passive"))
      (node (ref "U12") (pin "3") (pinfunction "ET_3") (pintype "passive"))
    )
    (net (code "52") (name "Net-(U1-V3)") (class "Default")
      (node (ref "C3") (pin "1") (pinfunction "1_1") (pintype "passive"))
      (node (ref "U1") (pin "4") (pinfunction "V3_4") (pintype "power_in"))
    )
    (net (code "53") (name "Net-(U1-XI)") (class "Default")
      (node (ref "C4") (pin "2") (pinfunction "2_2") (pintype "passive"))
      (node (ref "Q3") (pin "2") (pinfunction "2_2") (pintype "passive"))
      (node (ref "U1") (pin "7") (pinfunction "XI_7") (pintype "input"))
    )
    (net (code "54") (name "Net-(U1-XO)") (class "Default")
      (node (ref "C5") (pin "2") (pinfunction "2_2") (pintype "passive"))
      (node (ref "Q3") (pin "1") (pinfunction "1_1") (pintype "passive"))
      (node (ref "U1") (pin "8") (pinfunction "XO_8") (pintype "output"))
    )
    (net (code "55") (name "Net-(U4-A)") (class "Default")
      (node (ref "R11") (pin "1") (pinfunction "1_1") (pintype "passive"))
      (node (ref "U4") (pin "1") (pinfunction "A_1") (pintype "passive"))
    )
    (net (code "56") (name "Net-(U4-CT)") (class "Default")
      (node (ref "R12") (pin "2") (pinfunction "2_2") (pintype "passive"))
      (node (ref "U4") (pin "4") (pinfunction "CT_4") (pintype "passive"))
    )
    (net (code "57") (name "Net-(U5-A)") (class "Default")
      (node (ref "R13") (pin "1") (pinfunction "1_1") (pintype "passive"))
      (node (ref "U5") (pin "1") (pinfunction "A_1") (pintype "passive"))
    )
    (net (code "58") (name "Net-(U5-CT)") (class "Default")
      (node (ref "R14") (pin "2") (pinfunction "2_2") (pintype "passive"))
      (node (ref "U5") (pin "4") (pinfunction "CT_4") (pintype "passive"))
    )
    (net (code "59") (name "Net-(U6-A)") (class "Default")
      (node (ref "R23") (pin "1") (pinfunction "1_1") (pintype "passive"))
      (node (ref "U6") (pin "1") (pinfunction "A_1") (pintype "passive"))
    )
    (net (code "60") (name "Net-(U6-CT)") (class "Default")
      (node (ref "R24") (pin "2") (pinfunction "2_2") (pintype "passive"))
      (node (ref "U6") (pin "4") (pinfunction "CT_4") (pintype "passive"))
    )
    (net (code "61") (name "Net-(U7-V3)") (class "Default")
      (node (ref "C16") (pin "1") (pinfunction "1_1") (pintype "passive"))
      (node (ref "U7") (pin "4") (pinfunction "V3_4") (pintype "power_in"))
    )
    (net (code "62") (name "Net-(U7-XI)") (class "Default")
      (node (ref "C12") (pin "2") (pinfunction "2_2") (pintype "passive"))
      (node (ref "Q7") (pin "2") (pinfunction "2_2") (pintype "passive"))
      (node (ref "U7") (pin "7") (pinfunction "XI_7") (pintype "input"))
    )
    (net (code "63") (name "Net-(U7-XO)") (class "Default")
      (node (ref "C13") (pin "2") (pinfunction "2_2") (pintype "passive"))
      (node (ref "Q7") (pin "1") (pinfunction "1_1") (pintype "passive"))
      (node (ref "U7") (pin "8") (pinfunction "XO_8") (pintype "output"))
    )
    (net (code "64") (name "Net-(U11-A)") (class "Default")
      (node (ref "R22") (pin "1") (pinfunction "1_1") (pintype "passive"))
      (node (ref "U11") (pin "1") (pinfunction "A_1") (pintype "passive"))
    )
    (net (code "65") (name "Net-(U11-CT)") (class "Default")
      (node (ref "R29") (pin "2") (pinfunction "2_2") (pintype "passive"))
      (node (ref "U11") (pin "4") (pinfunction "CT_4") (pintype "passive"))
    )
    (net (code "66") (name "Net-(U12-A)") (class "Default")
      (node (ref "R30") (pin "1") (pinfunction "1_1") (pintype "passive"))
      (node (ref "U12") (pin "1") (pinfunction "A_1") (pintype "passive"))
    )
    (net (code "67") (name "Net-(U12-CT)") (class "Default")
      (node (ref "R31") (pin "2") (pinfunction "2_2") (pintype "passive"))
      (node (ref "U12") (pin "4") (pinfunction "CT_4") (pintype "passive"))
    )
    (net (code "68") (name "Net-(X7A-S)") (class "Default")
      (node (ref "MODUL-BATT1") (pin "BATT+") (pinfunction "BATT+_BATT+") (pintype "bidirectional"))
      (node (ref "X7") (pin "1") (pinfunction "S_1") (pintype "passive"))
    )
    (net (code "69") (name "OUT+") (class "Default")
      (node (ref "ADS1") (pin "VDD") (pinfunction "VDD_VDD") (pintype "bidirectional"))
      (node (ref "ADS2") (pin "VDD") (pinfunction "VDD_VDD") (pintype "bidirectional"))
      (node (ref "C19") (pin "1") (pinfunction "1_1") (pintype "passive"))
      (node (ref "C21") (pin "1") (pinfunction "1_1") (pintype "passive"))
      (node (ref "C6") (pin "+") (pinfunction "+_+") (pintype "passive"))
      (node (ref "C7") (pin "1") (pinfunction "1_1") (pintype "passive"))
      (node (ref "C8") (pin "1") (pinfunction "1_1") (pintype "passive"))
      (node (ref "D1") (pin "C") (pinfunction "K_C") (pintype "passive"))
      (node (ref "D13") (pin "C") (pinfunction "K_C") (pintype "passive"))
      (node (ref "D14") (pin "C") (pinfunction "K_C") (pintype "passive"))
      (node (ref "D2") (pin "C") (pinfunction "K_C") (pintype "passive"))
      (node (ref "D4") (pin "C") (pinfunction "K_C") (pintype "passive"))
      (node (ref "D5") (pin "C") (pinfunction "K_C") (pintype "passive"))
      (node (ref "D6") (pin "C") (pinfunction "K_C") (pintype "passive"))
      (node (ref "D7") (pin "C") (pinfunction "K_C") (pintype "passive"))
      (node (ref "D8") (pin "C") (pinfunction "K_C") (pintype "passive"))
      (node (ref "EBYTEE220-900T22D1") (pin "VCC") (pinfunction "VCC_VCC") (pintype "bidirectional"))
      (node (ref "EBYTEE220-900T22D2") (pin "VCC") (pinfunction "VCC_VCC") (pintype "bidirectional"))
      (node (ref "K1") (pin "1") (pinfunction "1_1") (pintype "passive"))
      (node (ref "K2") (pin "1") (pinfunction "1_1") (pintype "passive"))
      (node (ref "K3") (pin "A1") (pinfunction "A1_A1") (pintype "passive"))
      (node (ref "K4") (pin "1") (pinfunction "1_1") (pintype "passive"))
      (node (ref "K5") (pin "1") (pinfunction "1_1") (pintype "passive"))
      (node (ref "MODUL-BATT1") (pin "IN+") (pinfunction "IN+_IN+") (pintype "bidirectional"))
      (node (ref "NEO-6MGPS1") (pin "5V") (pinfunction "5V_5V") (pintype "bidirectional"))
      (node (ref "R12") (pin "1") (pinfunction "1_1") (pintype "passive"))
      (node (ref "R14") (pin "1") (pinfunction "1_1") (pintype "passive"))
      (node (ref "R24") (pin "1") (pinfunction "1_1") (pintype "passive"))
      (node (ref "R29") (pin "1") (pinfunction "1_1") (pintype "passive"))
      (node (ref "R3") (pin "2") (pinfunction "2_2") (pintype "passive"))
      (node (ref "R31") (pin "1") (pinfunction "1_1") (pintype "passive"))
      (node (ref "U10") (pin "8") (pinfunction "VDD_8") (pintype "power_in"))
      (node (ref "U3") (pin "3") (pinfunction "VIN_3") (pintype "input"))
      (node (ref "U8") (pin "3") (pinfunction "VIN_3") (pintype "input"))
      (node (ref "X6") (pin "1") (pinfunction "1_1") (pintype "passive"))
    )
    (net (code "70") (name "OUT-BATT") (class "Default")
      (node (ref "D8") (pin "A") (pinfunction "A_A") (pintype "passive"))
      (node (ref "MODUL-BATT1") (pin "OUT+") (pinfunction "OUT+_OUT+") (pintype "bidirectional"))
    )
    (net (code "71") (name "OUT1") (class "Default")
      (node (ref "SV1") (pin "1") (pinfunction "1_1") (pintype "passive"))
      (node (ref "U9") (pin "37") (pinfunction "IO23_37") (pintype "bidirectional"))
    )
    (net (code "72") (name "OUT2") (class "Default")
      (node (ref "SV1") (pin "2") (pinfunction "2_2") (pintype "passive"))
      (node (ref "U9") (pin "26") (pinfunction "IO4_26") (pintype "bidirectional"))
    )
    (net (code "73") (name "OUT3") (class "Default")
      (node (ref "SV1") (pin "3") (pinfunction "3_3") (pintype "passive"))
      (node (ref "U9") (pin "23") (pinfunction "IO15_23") (pintype "bidirectional"))
    )
    (net (code "74") (name "OUT4") (class "Default")
      (node (ref "SV1") (pin "4") (pinfunction "4_4") (pintype "passive"))
      (node (ref "U9") (pin "16") (pinfunction "IO13_16") (pintype "bidirectional"))
    )
    (net (code "75") (name "OUT5") (class "Default")
      (node (ref "SV1") (pin "5") (pinfunction "5_5") (pintype "passive"))
      (node (ref "U9") (pin "14") (pinfunction "IO12_14") (pintype "bidirectional"))
    )
    (net (code "76") (name "OUT6") (class "Default")
      (node (ref "SV1") (pin "6") (pinfunction "6_6") (pintype "passive"))
      (node (ref "U9") (pin "13") (pinfunction "IO14_13") (pintype "bidirectional"))
    )
    (net (code "77") (name "OUT7") (class "Default")
      (node (ref "SV1") (pin "7") (pinfunction "7_7") (pintype "passive"))
      (node (ref "U9") (pin "12") (pinfunction "IO27_12") (pintype "bidirectional"))
    )
    (net (code "78") (name "OUT8") (class "Default")
      (node (ref "SV1") (pin "8") (pinfunction "8_8") (pintype "passive"))
      (node (ref "U9") (pin "9") (pinfunction "IO33_9") (pintype "bidirectional"))
    )
    (net (code "79") (name "OUT9") (class "Default")
      (node (ref "SV1") (pin "9") (pinfunction "9_9") (pintype "passive"))
      (node (ref "U9") (pin "8") (pinfunction "IO32_8") (pintype "bidirectional"))
    )
    (net (code "80") (name "PB-PWR") (class "Default")
      (node (ref "R9") (pin "2") (pinfunction "2_2") (pintype "passive"))
      (node (ref "X3") (pin "3") (pinfunction "1_3") (pintype "passive"))
    )
    (net (code "81") (name "RTS") (class "Default")
      (node (ref "Q1") (pin "2") (pinfunction "E_2") (pintype "passive"))
      (node (ref "R2") (pin "1") (pinfunction "1_1") (pintype "passive"))
      (node (ref "U1") (pin "14") (pinfunction "~{RTS}_14") (pintype "output"))
    )
    (net (code "82") (name "RTS1") (class "Default")
      (node (ref "Q8") (pin "2") (pinfunction "E_2") (pintype "passive"))
      (node (ref "R26") (pin "1") (pinfunction "1_1") (pintype "passive"))
      (node (ref "U7") (pin "14") (pinfunction "~{RTS}_14") (pintype "output"))
    )
    (net (code "83") (name "RX") (class "Default")
      (node (ref "D10") (pin "C") (pinfunction "C_C") (pintype "passive"))
      (node (ref "U1") (pin "3") (pinfunction "RXD_3") (pintype "input"))
      (node (ref "U2") (pin "35") (pinfunction "TXD0_35") (pintype "bidirectional"))
    )
    (net (code "84") (name "RX1") (class "Default")
      (node (ref "D12") (pin "C") (pinfunction "C_C") (pintype "passive"))
      (node (ref "U7") (pin "3") (pinfunction "RXD_3") (pintype "input"))
      (node (ref "U9") (pin "35") (pinfunction "TXD0_35") (pintype "bidirectional"))
    )
    (net (code "85") (name "RXLORA_CONFIG") (class "Default")
      (node (ref "K1") (pin "S1") (pinfunction "S_S1") (pintype "passive"))
      (node (ref "X4") (pin "2") (pinfunction "1_2") (pintype "passive"))
    )
    (net (code "86") (name "RXLORA_MICRO") (class "Default")
      (node (ref "K1") (pin "O1") (pinfunction "O_O1") (pintype "passive"))
      (node (ref "U2") (pin "28") (pinfunction "IO17_28") (pintype "bidirectional"))
    )
    (net (code "87") (name "RX_GPS") (class "Default")
      (node (ref "K4") (pin "O2") (pinfunction "O_O2") (pintype "passive"))
      (node (ref "NEO-6MGPS1") (pin "RX") (pinfunction "RX_RX") (pintype "bidirectional"))
    )
    (net (code "88") (name "RX_LORA") (class "Default")
      (node (ref "EBYTEE220-900T22D1") (pin "RXD") (pinfunction "RXD_RXD") (pintype "bidirectional"))
      (node (ref "K1") (pin "P1") (pinfunction "P_P1") (pintype "passive"))
      (node (ref "SJ2") (pin "2") (pinfunction "2_2") (pintype "passive"))
    )
    (net (code "89") (name "RX_LORA1") (class "Default")
      (node (ref "K4") (pin "S2") (pinfunction "S_S2") (pintype "passive"))
      (node (ref "SJ2") (pin "1") (pinfunction "1_1") (pintype "passive"))
      (node (ref "SJ4") (pin "1") (pinfunction "1_1") (pintype "passive"))
    )
    (net (code "90") (name "RX_MICRO") (class "Default")
      (node (ref "U2") (pin "13") (pinfunction "IO14_13") (pintype "bidirectional"))
      (node (ref "U9") (pin "27") (pinfunction "IO16_27") (pintype "bidirectional"))
    )
    (net (code "91") (name "SCL") (class "Default")
      (node (ref "ADS1") (pin "SCL") (pinfunction "SCL_SCL") (pintype "bidirectional"))
      (node (ref "U10") (pin "10") (pinfunction "SCL_10") (pintype "input"))
      (node (ref "U2") (pin "36") (pinfunction "IO22_36") (pintype "bidirectional"))
      (node (ref "X6") (pin "3") (pinfunction "1_3") (pintype "passive"))
    )
    (net (code "92") (name "SCL1") (class "Default")
      (node (ref "ADS2") (pin "SCL") (pinfunction "SCL_SCL") (pintype "bidirectional"))
      (node (ref "U9") (pin "36") (pinfunction "IO22_36") (pintype "bidirectional"))
      (node (ref "X8") (pin "1") (pinfunction "1_1") (pintype "passive"))
    )
    (net (code "93") (name "SDA") (class "Default")
      (node (ref "ADS1") (pin "SDA") (pinfunction "SDA_SDA") (pintype "bidirectional"))
      (node (ref "U10") (pin "9") (pinfunction "SDA_9") (pintype "bidirectional"))
      (node (ref "U2") (pin "33") (pinfunction "IO21_33") (pintype "bidirectional"))
      (node (ref "X6") (pin "2") (pinfunction "1_2") (pintype "passive"))
    )
    (net (code "94") (name "SDA1") (class "Default")
      (node (ref "ADS2") (pin "SDA") (pinfunction "SDA_SDA") (pintype "bidirectional"))
      (node (ref "U9") (pin "33") (pinfunction "IO21_33") (pintype "bidirectional"))
      (node (ref "X8") (pin "2") (pinfunction "1_2") (pintype "passive"))
    )
    (net (code "95") (name "TX") (class "Default")
      (node (ref "D9") (pin "C") (pinfunction "C_C") (pintype "passive"))
      (node (ref "U1") (pin "2") (pinfunction "TXD_2") (pintype "output"))
      (node (ref "U2") (pin "34") (pinfunction "RXD0_34") (pintype "bidirectional"))
    )
    (net (code "96") (name "TX1") (class "Default")
      (node (ref "D11") (pin "C") (pinfunction "C_C") (pintype "passive"))
      (node (ref "U7") (pin "2") (pinfunction "TXD_2") (pintype "output"))
      (node (ref "U9") (pin "34") (pinfunction "RXD0_34") (pintype "bidirectional"))
    )
    (net (code "97") (name "TXLORA_CONFIG") (class "Default")
      (node (ref "K1") (pin "S2") (pinfunction "S_S2") (pintype "passive"))
      (node (ref "X4") (pin "1") (pinfunction "1_1") (pintype "passive"))
    )
    (net (code "98") (name "TXLORA_MICRO") (class "Default")
      (node (ref "K1") (pin "O2") (pinfunction "O_O2") (pintype "passive"))
      (node (ref "U2") (pin "27") (pinfunction "IO16_27") (pintype "bidirectional"))
    )
    (net (code "99") (name "TX_GPS") (class "Default")
      (node (ref "K4") (pin "O1") (pinfunction "O_O1") (pintype "passive"))
      (node (ref "NEO-6MGPS1") (pin "TX") (pinfunction "TX_TX") (pintype "bidirectional"))
    )
    (net (code "100") (name "TX_LORA") (class "Default")
      (node (ref "EBYTEE220-900T22D1") (pin "TXD") (pinfunction "TXD_TXD") (pintype "bidirectional"))
      (node (ref "K1") (pin "P2") (pinfunction "P_P2") (pintype "passive"))
      (node (ref "SJ1") (pin "2") (pinfunction "2_2") (pintype "passive"))
    )
    (net (code "101") (name "TX_LORA1") (class "Default")
      (node (ref "K4") (pin "S1") (pinfunction "S_S1") (pintype "passive"))
      (node (ref "SJ1") (pin "1") (pinfunction "1_1") (pintype "passive"))
      (node (ref "SJ3") (pin "1") (pinfunction "1_1") (pintype "passive"))
    )
    (net (code "102") (name "TX_MICRO") (class "Default")
      (node (ref "U2") (pin "23") (pinfunction "IO15_23") (pintype "bidirectional"))
      (node (ref "U9") (pin "28") (pinfunction "IO17_28") (pintype "bidirectional"))
    )
    (net (code "103") (name "USB1_N") (class "Default")
      (node (ref "J2") (pin "2") (pinfunction "D-_2") (pintype "passive"))
      (node (ref "U7") (pin "6") (pinfunction "UD-_6") (pintype "bidirectional"))
    )
    (net (code "104") (name "USB1_P") (class "Default")
      (node (ref "J2") (pin "3") (pinfunction "D+_3") (pintype "passive"))
      (node (ref "U7") (pin "5") (pinfunction "UD+_5") (pintype "bidirectional"))
    )
    (net (code "105") (name "USB_N") (class "Default")
      (node (ref "J1") (pin "2") (pinfunction "D-_2") (pintype "passive"))
      (node (ref "U1") (pin "6") (pinfunction "UD-_6") (pintype "bidirectional"))
    )
    (net (code "106") (name "USB_P") (class "Default")
      (node (ref "J1") (pin "3") (pinfunction "D+_3") (pintype "passive"))
      (node (ref "U1") (pin "5") (pinfunction "UD+_5") (pintype "bidirectional"))
    )
    (net (code "107") (name "VALVE") (class "Default")
      (node (ref "R13") (pin "2") (pinfunction "2_2") (pintype "passive"))
      (node (ref "U2") (pin "37") (pinfunction "IO23_37") (pintype "bidirectional"))
    )
    (net (code "108") (name "VALVE1") (class "Default")
      (node (ref "K2") (pin "S1") (pinfunction "S_S1") (pintype "passive"))
      (node (ref "X5") (pin "2") (pinfunction "1_2") (pintype "passive"))
    )
    (net (code "109") (name "VALVE2") (class "Default")
      (node (ref "K2") (pin "P1") (pinfunction "P_P1") (pintype "passive"))
      (node (ref "X5") (pin "1") (pinfunction "1_1") (pintype "passive"))
    )
    (net (code "110") (name "VCC") (class "Default")
      (node (ref "C9") (pin "1") (pinfunction "1_1") (pintype "passive"))
      (node (ref "R10") (pin "2") (pinfunction "2_2") (pintype "passive"))
      (node (ref "R17") (pin "2") (pinfunction "2_2") (pintype "passive"))
      (node (ref "R18") (pin "2") (pinfunction "2_2") (pintype "passive"))
      (node (ref "R4") (pin "2") (pinfunction "2_2") (pintype "passive"))
      (node (ref "R5") (pin "2") (pinfunction "2_2") (pintype "passive"))
      (node (ref "R6") (pin "2") (pinfunction "2_2") (pintype "passive"))
      (node (ref "R7") (pin "2") (pinfunction "2_2") (pintype "passive"))
      (node (ref "R8") (pin "2") (pinfunction "2_2") (pintype "passive"))
      (node (ref "U2") (pin "2") (pinfunction "3V3_2") (pintype "power_in"))
      (node (ref "U3") (pin "2") (pinfunction "VOUT_2") (pintype "output"))
      (node (ref "U3") (pin "4") (pinfunction "VOUT_4") (pintype "output"))
    )
    (net (code "111") (name "VCC1") (class "Default")
      (node (ref "C20") (pin "1") (pinfunction "1_1") (pintype "passive"))
      (node (ref "R19") (pin "2") (pinfunction "2_2") (pintype "passive"))
      (node (ref "R20") (pin "2") (pinfunction "2_2") (pintype "passive"))
      (node (ref "R27") (pin "2") (pinfunction "2_2") (pintype "passive"))
      (node (ref "R28") (pin "2") (pinfunction "2_2") (pintype "passive"))
      (node (ref "U8") (pin "2") (pinfunction "VOUT_2") (pintype "output"))
      (node (ref "U8") (pin "4") (pinfunction "VOUT_4") (pintype "output"))
      (node (ref "U9") (pin "2") (pinfunction "3V3_2") (pintype "power_in"))
    )
    (net (code "112") (name "VUSB") (class "Default")
      (node (ref "C1") (pin "1") (pinfunction "1_1") (pintype "passive"))
      (node (ref "C2") (pin "+") (pinfunction "+_+") (pintype "passive"))
      (node (ref "D2") (pin "A") (pinfunction "A_A") (pintype "passive"))
      (node (ref "J1") (pin "1") (pinfunction "VUSB_1") (pintype "passive"))
      (node (ref "U1") (pin "16") (pinfunction "VCC_16") (pintype "power_in"))
    )
    (net (code "113") (name "VUSB1") (class "Default")
      (node (ref "C14") (pin "1") (pinfunction "1_1") (pintype "passive"))
      (node (ref "C15") (pin "+") (pinfunction "+_+") (pintype "passive"))
      (node (ref "D7") (pin "A") (pinfunction "A_A") (pintype "passive"))
      (node (ref "J2") (pin "1") (pinfunction "VUSB_1") (pintype "passive"))
      (node (ref "U7") (pin "16") (pinfunction "VCC_16") (pintype "power_in"))
    )
    (net (code "114") (name "unconnected-(ADS1-PadALRT)") (class "Default")
      (node (ref "ADS1") (pin "ALRT") (pinfunction "ALRT_ALRT") (pintype "bidirectional"))
    )
    (net (code "115") (name "unconnected-(ADS2-PadA1)") (class "Default")
      (node (ref "ADS2") (pin "A1") (pinfunction "A1_A1") (pintype "bidirectional"))
    )
    (net (code "116") (name "unconnected-(ADS2-PadA2)") (class "Default")
      (node (ref "ADS2") (pin "A2") (pinfunction "A2_A2") (pintype "bidirectional"))
    )
    (net (code "117") (name "unconnected-(ADS2-PadA3)") (class "Default")
      (node (ref "ADS2") (pin "A3") (pinfunction "A3_A3") (pintype "bidirectional"))
    )
    (net (code "118") (name "unconnected-(ADS2-PadALRT)") (class "Default")
      (node (ref "ADS2") (pin "ALRT") (pinfunction "ALRT_ALRT") (pintype "bidirectional"))
    )
    (net (code "119") (name "unconnected-(EBYTEE220-900T22D1-PadAUX)") (class "Default")
      (node (ref "EBYTEE220-900T22D1") (pin "AUX") (pinfunction "AUX_AUX") (pintype "bidirectional"))
    )
    (net (code "120") (name "unconnected-(EBYTEE220-900T22D2-PadAUX)") (class "Default")
      (node (ref "EBYTEE220-900T22D2") (pin "AUX") (pinfunction "AUX_AUX") (pintype "bidirectional"))
    )
    (net (code "121") (name "unconnected-(J1-ID-Pad4)") (class "Default")
      (node (ref "J1") (pin "4") (pinfunction "ID_4") (pintype "passive"))
    )
    (net (code "122") (name "unconnected-(J2-ID-Pad4)") (class "Default")
      (node (ref "J2") (pin "4") (pinfunction "ID_4") (pintype "passive"))
    )
    (net (code "123") (name "unconnected-(K2B-O-PadO1)") (class "Default")
      (node (ref "K2") (pin "O1") (pinfunction "O_O1") (pintype "passive"))
    )
    (net (code "124") (name "unconnected-(K2C-O-PadO2)") (class "Default")
      (node (ref "K2") (pin "O2") (pinfunction "O_O2") (pintype "passive"))
    )
    (net (code "125") (name "unconnected-(K2C-P-PadP2)") (class "Default")
      (node (ref "K2") (pin "P2") (pinfunction "P_P2") (pintype "passive"))
    )
    (net (code "126") (name "unconnected-(K2C-S-PadS2)") (class "Default")
      (node (ref "K2") (pin "S2") (pinfunction "S_S2") (pintype "passive"))
    )
    (net (code "127") (name "unconnected-(K3-PadNC)") (class "Default")
      (node (ref "K3") (pin "NC") (pinfunction "NC_NC") (pintype "passive"))
    )
    (net (code "128") (name "unconnected-(U1-RS232-Pad15)") (class "Default")
      (node (ref "U1") (pin "15") (pinfunction "RS232_15") (pintype "input"))
    )
    (net (code "129") (name "unconnected-(U1-~{CTS}-Pad9)") (class "Default")
      (node (ref "U1") (pin "9") (pinfunction "~{CTS}_9") (pintype "input"))
    )
    (net (code "130") (name "unconnected-(U1-~{DCD}-Pad12)") (class "Default")
      (node (ref "U1") (pin "12") (pinfunction "~{DCD}_12") (pintype "input"))
    )
    (net (code "131") (name "unconnected-(U1-~{DSR}-Pad10)") (class "Default")
      (node (ref "U1") (pin "10") (pinfunction "~{DSR}_10") (pintype "input"))
    )
    (net (code "132") (name "unconnected-(U1-~{RI}-Pad11)") (class "Default")
      (node (ref "U1") (pin "11") (pinfunction "~{RI}_11") (pintype "input"))
    )
    (net (code "133") (name "unconnected-(U2-IO2-Pad24)") (class "Default")
      (node (ref "U2") (pin "24") (pinfunction "IO2_24") (pintype "bidirectional"))
    )
    (net (code "134") (name "unconnected-(U2-IO4-Pad26)") (class "Default")
      (node (ref "U2") (pin "26") (pinfunction "IO4_26") (pintype "bidirectional"))
    )
    (net (code "135") (name "unconnected-(U2-IO5-Pad29)") (class "Default")
      (node (ref "U2") (pin "29") (pinfunction "IO5_29") (pintype "bidirectional"))
    )
    (net (code "136") (name "unconnected-(U2-IO12-Pad14)") (class "Default")
      (node (ref "U2") (pin "14") (pinfunction "IO12_14") (pintype "bidirectional"))
    )
    (net (code "137") (name "unconnected-(U2-IO13-Pad16)") (class "Default")
      (node (ref "U2") (pin "16") (pinfunction "IO13_16") (pintype "bidirectional"))
    )
    (net (code "138") (name "unconnected-(U2-IO19-Pad31)") (class "Default")
      (node (ref "U2") (pin "31") (pinfunction "IO19_31") (pintype "bidirectional"))
    )
    (net (code "139") (name "unconnected-(U2-IO34-Pad6)") (class "Default")
      (node (ref "U2") (pin "6") (pinfunction "IO34_6") (pintype "input"))
    )
    (net (code "140") (name "unconnected-(U2-IO35-Pad7)") (class "Default")
      (node (ref "U2") (pin "7") (pinfunction "IO35_7") (pintype "input"))
    )
    (net (code "141") (name "unconnected-(U2-SCK{slash}CLK-Pad20)") (class "Default")
      (node (ref "U2") (pin "20") (pinfunction "SCK/CLK_20") (pintype "bidirectional"))
    )
    (net (code "142") (name "unconnected-(U2-SCS{slash}CMD-Pad19)") (class "Default")
      (node (ref "U2") (pin "19") (pinfunction "SCS/CMD_19") (pintype "bidirectional"))
    )
    (net (code "143") (name "unconnected-(U2-SDI{slash}SD1-Pad22)") (class "Default")
      (node (ref "U2") (pin "22") (pinfunction "SDI/SD1_22") (pintype "bidirectional"))
    )
    (net (code "144") (name "unconnected-(U2-SDO{slash}SD0-Pad21)") (class "Default")
      (node (ref "U2") (pin "21") (pinfunction "SDO/SD0_21") (pintype "bidirectional"))
    )
    (net (code "145") (name "unconnected-(U2-SENSOR_VN-Pad5)") (class "Default")
      (node (ref "U2") (pin "5") (pinfunction "SENSOR_VN_5") (pintype "input"))
    )
    (net (code "146") (name "unconnected-(U2-SENSOR_VP-Pad4)") (class "Default")
      (node (ref "U2") (pin "4") (pinfunction "SENSOR_VP_4") (pintype "input"))
    )
    (net (code "147") (name "unconnected-(U2-SHD{slash}SD2-Pad17)") (class "Default")
      (node (ref "U2") (pin "17") (pinfunction "SHD/SD2_17") (pintype "bidirectional"))
    )
    (net (code "148") (name "unconnected-(U2-SWP{slash}SD3-Pad18)") (class "Default")
      (node (ref "U2") (pin "18") (pinfunction "SWP/SD3_18") (pintype "bidirectional"))
    )
    (net (code "149") (name "unconnected-(U7-RS232-Pad15)") (class "Default")
      (node (ref "U7") (pin "15") (pinfunction "RS232_15") (pintype "input"))
    )
    (net (code "150") (name "unconnected-(U7-~{CTS}-Pad9)") (class "Default")
      (node (ref "U7") (pin "9") (pinfunction "~{CTS}_9") (pintype "input"))
    )
    (net (code "151") (name "unconnected-(U7-~{DCD}-Pad12)") (class "Default")
      (node (ref "U7") (pin "12") (pinfunction "~{DCD}_12") (pintype "input"))
    )
    (net (code "152") (name "unconnected-(U7-~{DSR}-Pad10)") (class "Default")
      (node (ref "U7") (pin "10") (pinfunction "~{DSR}_10") (pintype "input"))
    )
    (net (code "153") (name "unconnected-(U7-~{RI}-Pad11)") (class "Default")
      (node (ref "U7") (pin "11") (pinfunction "~{RI}_11") (pintype "input"))
    )
    (net (code "154") (name "unconnected-(U9-IO34-Pad6)") (class "Default")
      (node (ref "U9") (pin "6") (pinfunction "IO34_6") (pintype "input"))
    )
    (net (code "155") (name "unconnected-(U9-IO35-Pad7)") (class "Default")
      (node (ref "U9") (pin "7") (pinfunction "IO35_7") (pintype "input"))
    )
    (net (code "156") (name "unconnected-(U9-SCK{slash}CLK-Pad20)") (class "Default")
      (node (ref "U9") (pin "20") (pinfunction "SCK/CLK_20") (pintype "bidirectional"))
    )
    (net (code "157") (name "unconnected-(U9-SCS{slash}CMD-Pad19)") (class "Default")
      (node (ref "U9") (pin "19") (pinfunction "SCS/CMD_19") (pintype "bidirectional"))
    )
    (net (code "158") (name "unconnected-(U9-SDI{slash}SD1-Pad22)") (class "Default")
      (node (ref "U9") (pin "22") (pinfunction "SDI/SD1_22") (pintype "bidirectional"))
    )
    (net (code "159") (name "unconnected-(U9-SDO{slash}SD0-Pad21)") (class "Default")
      (node (ref "U9") (pin "21") (pinfunction "SDO/SD0_21") (pintype "bidirectional"))
    )
    (net (code "160") (name "unconnected-(U9-SENSOR_VN-Pad5)") (class "Default")
      (node (ref "U9") (pin "5") (pinfunction "SENSOR_VN_5") (pintype "input"))
    )
    (net (code "161") (name "unconnected-(U9-SENSOR_VP-Pad4)") (class "Default")
      (node (ref "U9") (pin "4") (pinfunction "SENSOR_VP_4") (pintype "input"))
    )
    (net (code "162") (name "unconnected-(U9-SHD{slash}SD2-Pad17)") (class "Default")
      (node (ref "U9") (pin "17") (pinfunction "SHD/SD2_17") (pintype "bidirectional"))
    )
    (net (code "163") (name "unconnected-(U9-SWP{slash}SD3-Pad18)") (class "Default")
      (node (ref "U9") (pin "18") (pinfunction "SWP/SD3_18") (pintype "bidirectional"))
    )
    (net (code "164") (name "unconnected-(U10-AIN1-Pad5)") (class "Default")
      (node (ref "U10") (pin "5") (pinfunction "AIN1_5") (pintype "input"))
    )
    (net (code "165") (name "unconnected-(U10-AIN2-Pad6)") (class "Default")
      (node (ref "U10") (pin "6") (pinfunction "AIN2_6") (pintype "input"))
    )
    (net (code "166") (name "unconnected-(U10-AIN3-Pad7)") (class "Default")
      (node (ref "U10") (pin "7") (pinfunction "AIN3_7") (pintype "input"))
    )
    (net (code "167") (name "unconnected-(U10-ALERT{slash}RDY-Pad2)") (class "Default")
      (node (ref "U10") (pin "2") (pinfunction "ALERT/RDY_2") (pintype "output"))
    )
  )
)
